# Whisker_Stimulator.net
KiCad netlist of a schematic drawn in EAGLE
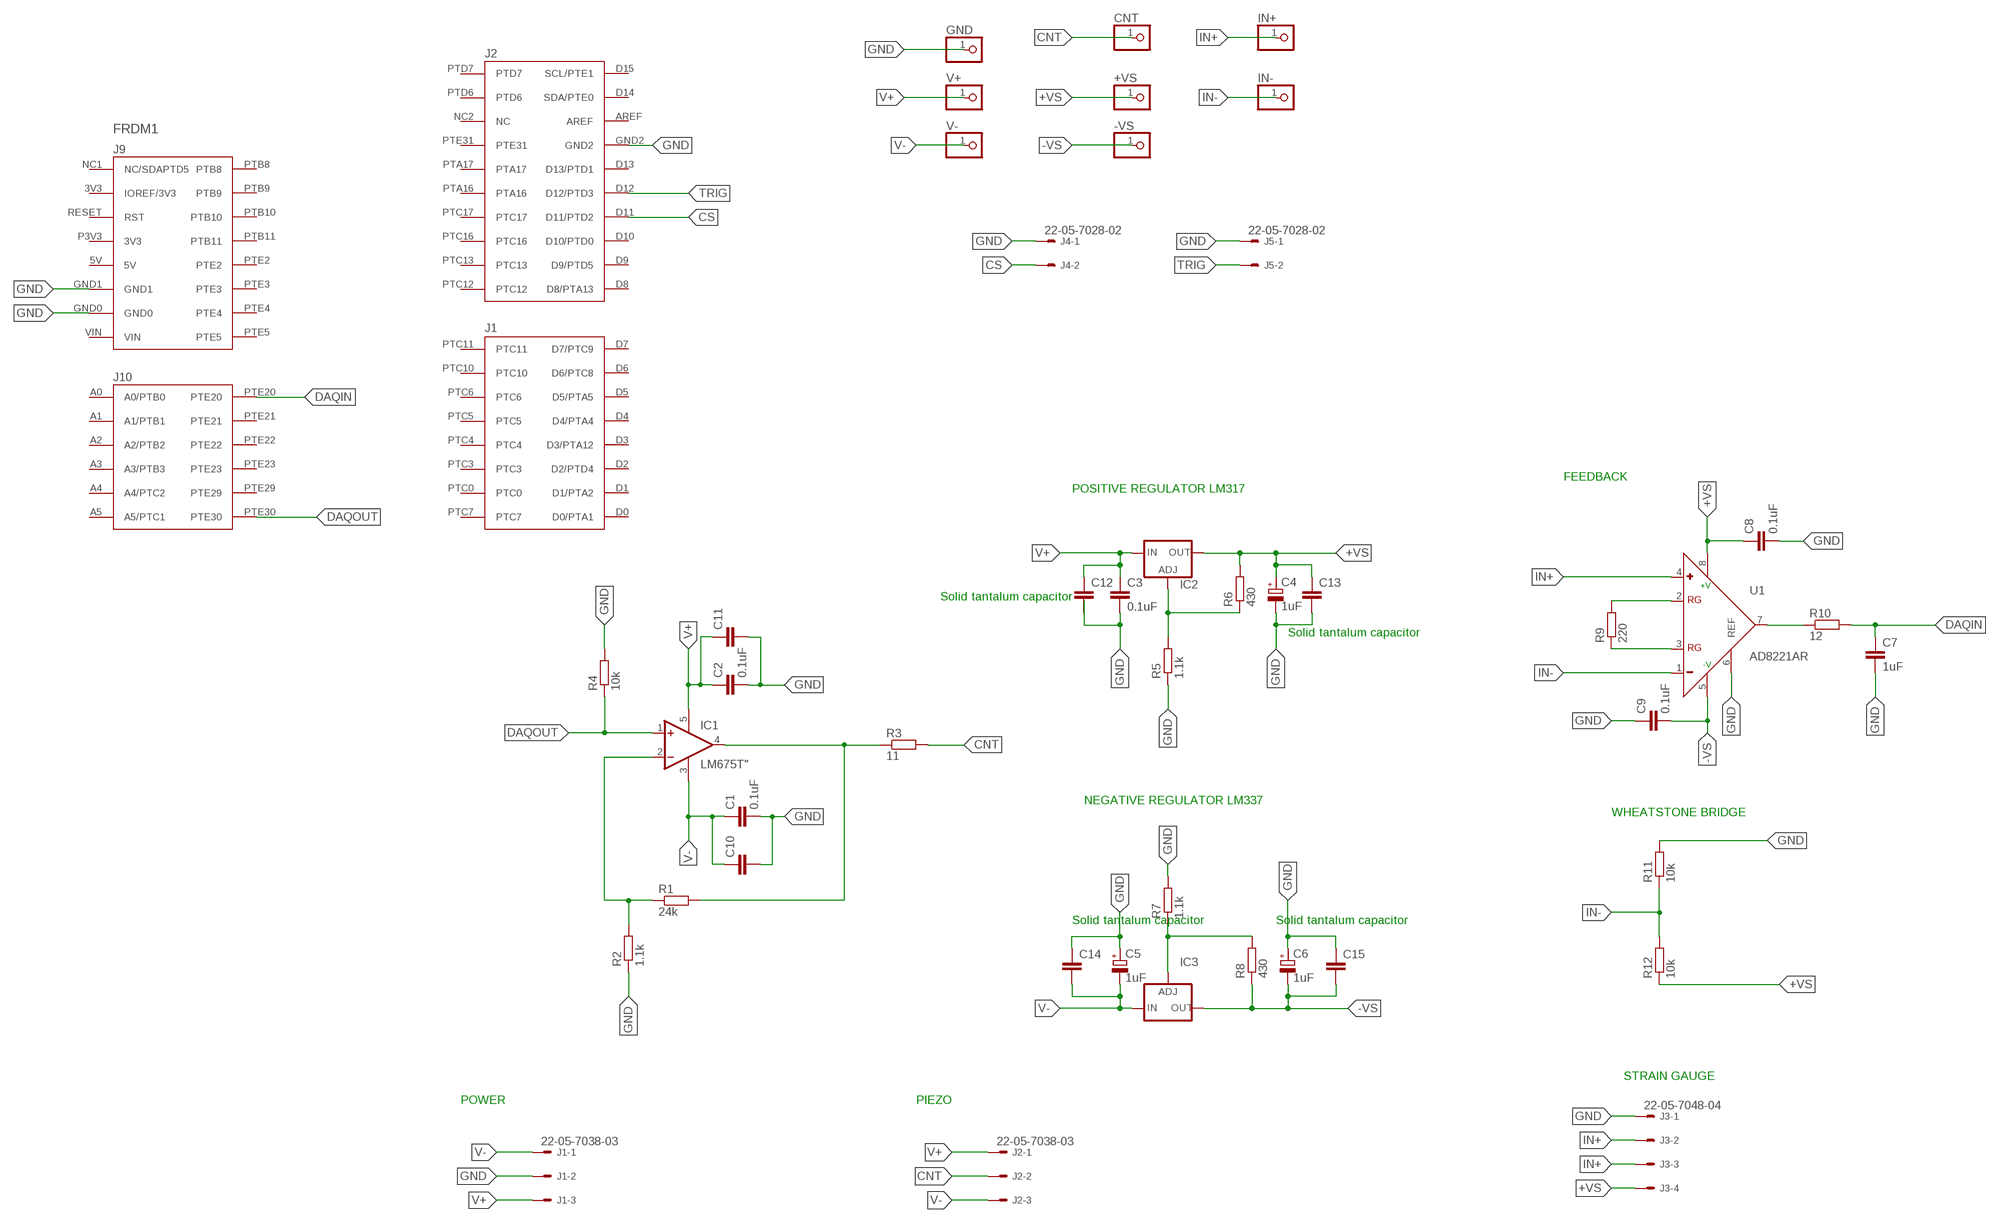
[diagram p0: schematic, sheet 1]

(export (version "E")
  (design (tool "Eeschema 10.0.6"))
  (components
    (comp (ref "+VS")
      (value "PINHD-1X1")
      (footprint "eagle-import:1X01")
      (libsource (lib "eagle-import") (part "PINHD-1X1"))
    )
    (comp (ref "-VS")
      (value "PINHD-1X1")
      (footprint "eagle-import:1X01")
      (libsource (lib "eagle-import") (part "PINHD-1X1"))
    )
    (comp (ref "C1")
      (value "0.1uF")
      (footprint "eagle-import:C0805")
      (libsource (lib "eagle-import") (part "C-EUC0805"))
    )
    (comp (ref "C2")
      (value "0.1uF")
      (footprint "eagle-import:C0805")
      (libsource (lib "eagle-import") (part "C-EUC0805"))
    )
    (comp (ref "C3")
      (value "0.1uF")
      (footprint "eagle-import:C0805")
      (libsource (lib "eagle-import") (part "C-EUC0805"))
    )
    (comp (ref "C4")
      (value "1uF")
      (footprint "eagle-import:E2,5RE")
      (libsource (lib "eagle-import") (part "CPOL-EUE2.5-4V"))
    )
    (comp (ref "C5")
      (value "1uF")
      (footprint "eagle-import:E2,5RE")
      (libsource (lib "eagle-import") (part "CPOL-EUE2.5-4V"))
    )
    (comp (ref "C6")
      (value "1uF")
      (footprint "eagle-import:E2,5RE")
      (libsource (lib "eagle-import") (part "CPOL-EUE2.5-4V"))
    )
    (comp (ref "C7")
      (value "1uF")
      (footprint "eagle-import:C0805")
      (libsource (lib "eagle-import") (part "C-EUC0805"))
    )
    (comp (ref "C8")
      (value "0.1uF")
      (footprint "eagle-import:C0805")
      (libsource (lib "eagle-import") (part "C-EUC0805"))
    )
    (comp (ref "C9")
      (value "0.1uF")
      (footprint "eagle-import:C0805")
      (libsource (lib "eagle-import") (part "C-EUC0805"))
    )
    (comp (ref "C10")
      (value "0.1uF")
      (footprint "eagle-import:C050-024X044")
      (libsource (lib "eagle-import") (part "C-EU050-024X044"))
    )
    (comp (ref "C11")
      (value "0.1uF")
      (footprint "eagle-import:C050-024X044")
      (libsource (lib "eagle-import") (part "C-EU050-024X044"))
    )
    (comp (ref "C12")
      (value "0.1uF")
      (footprint "eagle-import:C050-024X044")
      (libsource (lib "eagle-import") (part "C-EU050-024X044"))
    )
    (comp (ref "C13")
      (value "0.1uF")
      (footprint "eagle-import:C050-024X044")
      (libsource (lib "eagle-import") (part "C-EU050-024X044"))
    )
    (comp (ref "C14")
      (value "0.1uF")
      (footprint "eagle-import:C050-024X044")
      (libsource (lib "eagle-import") (part "C-EU050-024X044"))
    )
    (comp (ref "C15")
      (value "0.1uF")
      (footprint "eagle-import:C050-024X044")
      (libsource (lib "eagle-import") (part "C-EU050-024X044"))
    )
    (comp (ref "CNT")
      (value "PINHD-1X1")
      (footprint "eagle-import:1X01")
      (libsource (lib "eagle-import") (part "PINHD-1X1"))
    )
    (comp (ref "FRDM1")
      (value "FRDM-KL25ZNORMAL")
      (footprint "eagle-import:FRDM_KL25Z_NORMAL")
      (libsource (lib "eagle-import") (part "FRDM-KL25ZNORMAL"))
    )
    (comp (ref "GND")
      (value "PINHD-1X1")
      (footprint "eagle-import:1X01")
      (libsource (lib "eagle-import") (part "PINHD-1X1"))
    )
    (comp (ref "IC1")
      (value "LM675T\"")
      (footprint "eagle-import:CB360")
      (libsource (lib "eagle-import") (part "LM675T{dblquote}"))
    )
    (comp (ref "IC2")
      (value "LM317TS")
      (footprint "eagle-import:317TS")
      (libsource (lib "eagle-import") (part "LM317TS"))
    )
    (comp (ref "IC3")
      (value "LM337TS")
      (footprint "eagle-import:337TS")
      (libsource (lib "eagle-import") (part "LM337TS"))
    )
    (comp (ref "IN+")
      (value "PINHD-1X1")
      (footprint "eagle-import:1X01")
      (libsource (lib "eagle-import") (part "PINHD-1X1"))
    )
    (comp (ref "IN-")
      (value "PINHD-1X1")
      (footprint "eagle-import:1X01")
      (libsource (lib "eagle-import") (part "PINHD-1X1"))
    )
    (comp (ref "J1")
      (value "22-05-7038-03")
      (footprint "eagle-import:7395-03")
      (libsource (lib "eagle-import") (part "22-?-0305-7038"))
    )
    (comp (ref "J2")
      (value "22-05-7038-03")
      (footprint "eagle-import:7395-03")
      (libsource (lib "eagle-import") (part "22-?-0305-7038"))
    )
    (comp (ref "J3")
      (value "22-05-7048-04")
      (footprint "eagle-import:7395-04")
      (libsource (lib "eagle-import") (part "22-?-0405-7048"))
    )
    (comp (ref "J4")
      (value "22-05-7028-02")
      (footprint "eagle-import:7395-02")
      (libsource (lib "eagle-import") (part "22-?-0205-7028"))
    )
    (comp (ref "J5")
      (value "22-05-7028-02")
      (footprint "eagle-import:7395-02")
      (libsource (lib "eagle-import") (part "22-?-0205-7028"))
    )
    (comp (ref "R1")
      (value "24k")
      (footprint "eagle-import:R0805")
      (libsource (lib "eagle-import") (part "R-EU_R0805"))
    )
    (comp (ref "R2")
      (value "1.1k")
      (footprint "eagle-import:R0805")
      (libsource (lib "eagle-import") (part "R-EU_R0805"))
    )
    (comp (ref "R3")
      (value "11")
      (footprint "eagle-import:VMTA55")
      (libsource (lib "eagle-import") (part "R-EU_VMTA55"))
    )
    (comp (ref "R4")
      (value "10k")
      (footprint "eagle-import:R0805")
      (libsource (lib "eagle-import") (part "R-EU_R0805"))
    )
    (comp (ref "R5")
      (value "1.1k")
      (footprint "eagle-import:R0805")
      (libsource (lib "eagle-import") (part "R-EU_R0805"))
    )
    (comp (ref "R6")
      (value "430")
      (footprint "eagle-import:R0805")
      (libsource (lib "eagle-import") (part "R-EU_R0805"))
    )
    (comp (ref "R7")
      (value "1.1k")
      (footprint "eagle-import:R0805")
      (libsource (lib "eagle-import") (part "R-EU_R0805"))
    )
    (comp (ref "R8")
      (value "430")
      (footprint "eagle-import:R0805")
      (libsource (lib "eagle-import") (part "R-EU_R0805"))
    )
    (comp (ref "R9")
      (value "220")
      (footprint "eagle-import:R0805")
      (libsource (lib "eagle-import") (part "R-EU_R0805"))
    )
    (comp (ref "R10")
      (value "12")
      (footprint "eagle-import:R0805")
      (libsource (lib "eagle-import") (part "R-EU_R0805"))
    )
    (comp (ref "R11")
      (value "10k")
      (footprint "eagle-import:R0805")
      (libsource (lib "eagle-import") (part "R-EU_R0805"))
    )
    (comp (ref "R12")
      (value "10k")
      (footprint "eagle-import:R0805")
      (libsource (lib "eagle-import") (part "R-EU_R0805"))
    )
    (comp (ref "U1")
      (value "AD8221AR")
      (footprint "eagle-import:SO8")
      (libsource (lib "eagle-import") (part "AD8221AR"))
    )
    (comp (ref "V+")
      (value "PINHD-1X1")
      (footprint "eagle-import:1X01")
      (libsource (lib "eagle-import") (part "PINHD-1X1"))
    )
    (comp (ref "V-")
      (value "PINHD-1X1")
      (footprint "eagle-import:1X01")
      (libsource (lib "eagle-import") (part "PINHD-1X1"))
    )
  )
  (nets
    (net (code "1") (name "+VS") (class "Default")
      (node (ref "+VS") (pin "1") (pinfunction "1_1") (pintype "passive"))
      (node (ref "C13") (pin "1") (pinfunction "1_1") (pintype "passive"))
      (node (ref "C4") (pin "+") (pinfunction "+_+") (pintype "passive"))
      (node (ref "C8") (pin "1") (pinfunction "1_1") (pintype "passive"))
      (node (ref "IC2") (pin "2") (pinfunction "OUT_2") (pintype "passive"))
      (node (ref "J3") (pin "4") (pinfunction "S_4") (pintype "passive"))
      (node (ref "R12") (pin "1") (pinfunction "1_1") (pintype "passive"))
      (node (ref "R6") (pin "2") (pinfunction "2_2") (pintype "passive"))
      (node (ref "U1") (pin "8") (pinfunction "+V_8") (pintype "power_in"))
    )
    (net (code "2") (name "-VS") (class "Default")
      (node (ref "-VS") (pin "1") (pinfunction "1_1") (pintype "passive"))
      (node (ref "C15") (pin "2") (pinfunction "2_2") (pintype "passive"))
      (node (ref "C6") (pin "-") (pinfunction "-_-") (pintype "passive"))
      (node (ref "C9") (pin "2") (pinfunction "2_2") (pintype "passive"))
      (node (ref "IC3") (pin "3") (pinfunction "OUT_3") (pintype "passive"))
      (node (ref "R8") (pin "1") (pinfunction "1_1") (pintype "passive"))
      (node (ref "U1") (pin "5") (pinfunction "-V_5") (pintype "power_in"))
    )
    (net (code "3") (name "CNT") (class "Default")
      (node (ref "CNT") (pin "1") (pinfunction "1_1") (pintype "passive"))
      (node (ref "J2") (pin "2") (pinfunction "S_2") (pintype "passive"))
      (node (ref "R3") (pin "2") (pinfunction "2_2") (pintype "passive"))
    )
    (net (code "4") (name "CS") (class "Default")
      (node (ref "FRDM1") (pin "D11") (pinfunction "D11/PTD2_D11") (pintype "bidirectional"))
      (node (ref "J4") (pin "2") (pinfunction "S_2") (pintype "passive"))
    )
    (net (code "5") (name "DAQIN") (class "Default")
      (node (ref "C7") (pin "1") (pinfunction "1_1") (pintype "passive"))
      (node (ref "FRDM1") (pin "PTE20") (pinfunction "PTE20_PTE20") (pintype "bidirectional"))
      (node (ref "R10") (pin "2") (pinfunction "2_2") (pintype "passive"))
    )
    (net (code "6") (name "DAQOUT") (class "Default")
      (node (ref "FRDM1") (pin "PTE30") (pinfunction "PTE30_PTE30") (pintype "bidirectional"))
      (node (ref "IC1") (pin "1") (pinfunction "+IN_1") (pintype "input"))
      (node (ref "R4") (pin "1") (pinfunction "1_1") (pintype "passive"))
    )
    (net (code "7") (name "GND") (class "Default")
      (node (ref "C1") (pin "2") (pinfunction "2_2") (pintype "passive"))
      (node (ref "C10") (pin "2") (pinfunction "2_2") (pintype "passive"))
      (node (ref "C11") (pin "2") (pinfunction "2_2") (pintype "passive"))
      (node (ref "C12") (pin "2") (pinfunction "2_2") (pintype "passive"))
      (node (ref "C13") (pin "2") (pinfunction "2_2") (pintype "passive"))
      (node (ref "C14") (pin "1") (pinfunction "1_1") (pintype "passive"))
      (node (ref "C15") (pin "1") (pinfunction "1_1") (pintype "passive"))
      (node (ref "C2") (pin "2") (pinfunction "2_2") (pintype "passive"))
      (node (ref "C3") (pin "2") (pinfunction "2_2") (pintype "passive"))
      (node (ref "C4") (pin "-") (pinfunction "-_-") (pintype "passive"))
      (node (ref "C5") (pin "+") (pinfunction "+_+") (pintype "passive"))
      (node (ref "C6") (pin "+") (pinfunction "+_+") (pintype "passive"))
      (node (ref "C7") (pin "2") (pinfunction "2_2") (pintype "passive"))
      (node (ref "C8") (pin "2") (pinfunction "2_2") (pintype "passive"))
      (node (ref "C9") (pin "1") (pinfunction "1_1") (pintype "passive"))
      (node (ref "FRDM1") (pin "GND0") (pinfunction "GND0_GND0") (pintype "bidirectional"))
      (node (ref "FRDM1") (pin "GND1") (pinfunction "GND1_GND1") (pintype "bidirectional"))
      (node (ref "FRDM1") (pin "GND2") (pinfunction "GND2_GND2") (pintype "bidirectional"))
      (node (ref "GND") (pin "1") (pinfunction "1_1") (pintype "passive"))
      (node (ref "J1") (pin "2") (pinfunction "S_2") (pintype "passive"))
      (node (ref "J3") (pin "1") (pinfunction "S_1") (pintype "passive"))
      (node (ref "J4") (pin "1") (pinfunction "S_1") (pintype "passive"))
      (node (ref "J5") (pin "1") (pinfunction "S_1") (pintype "passive"))
      (node (ref "R11") (pin "2") (pinfunction "2_2") (pintype "passive"))
      (node (ref "R2") (pin "1") (pinfunction "1_1") (pintype "passive"))
      (node (ref "R4") (pin "2") (pinfunction "2_2") (pintype "passive"))
      (node (ref "R5") (pin "1") (pinfunction "1_1") (pintype "passive"))
      (node (ref "R7") (pin "2") (pinfunction "2_2") (pintype "passive"))
      (node (ref "U1") (pin "6") (pinfunction "REF_6") (pintype "passive"))
    )
    (net (code "8") (name "IN+") (class "Default")
      (node (ref "IN+") (pin "1") (pinfunction "1_1") (pintype "passive"))
      (node (ref "J3") (pin "2") (pinfunction "S_2") (pintype "passive"))
      (node (ref "J3") (pin "3") (pinfunction "S_3") (pintype "passive"))
      (node (ref "U1") (pin "4") (pinfunction "+_4") (pintype "input"))
    )
    (net (code "9") (name "IN-") (class "Default")
      (node (ref "IN-") (pin "1") (pinfunction "1_1") (pintype "passive"))
      (node (ref "R11") (pin "1") (pinfunction "1_1") (pintype "passive"))
      (node (ref "R12") (pin "2") (pinfunction "2_2") (pintype "passive"))
      (node (ref "U1") (pin "1") (pinfunction "-_1") (pintype "input"))
    )
    (net (code "10") (name "Net-(IC1--IN)") (class "Default")
      (node (ref "IC1") (pin "2") (pinfunction "-IN_2") (pintype "input"))
      (node (ref "R1") (pin "1") (pinfunction "1_1") (pintype "passive"))
      (node (ref "R2") (pin "2") (pinfunction "2_2") (pintype "passive"))
    )
    (net (code "11") (name "Net-(IC1-OUT)") (class "Default")
      (node (ref "IC1") (pin "4") (pinfunction "OUT_4") (pintype "output"))
      (node (ref "R1") (pin "2") (pinfunction "2_2") (pintype "passive"))
      (node (ref "R3") (pin "1") (pinfunction "1_1") (pintype "passive"))
    )
    (net (code "12") (name "Net-(IC2-ADJ)") (class "Default")
      (node (ref "IC2") (pin "1") (pinfunction "ADJ_1") (pintype "input"))
      (node (ref "R5") (pin "2") (pinfunction "2_2") (pintype "passive"))
      (node (ref "R6") (pin "1") (pinfunction "1_1") (pintype "passive"))
    )
    (net (code "13") (name "Net-(IC3-ADJ)") (class "Default")
      (node (ref "IC3") (pin "1") (pinfunction "ADJ_1") (pintype "input"))
      (node (ref "R7") (pin "1") (pinfunction "1_1") (pintype "passive"))
      (node (ref "R8") (pin "2") (pinfunction "2_2") (pintype "passive"))
    )
    (net (code "14") (name "Net-(R9-Pad1)") (class "Default")
      (node (ref "R9") (pin "1") (pinfunction "1_1") (pintype "passive"))
      (node (ref "U1") (pin "3") (pinfunction "RG_3") (pintype "passive"))
    )
    (net (code "15") (name "Net-(R9-Pad2)") (class "Default")
      (node (ref "R9") (pin "2") (pinfunction "2_2") (pintype "passive"))
      (node (ref "U1") (pin "2") (pinfunction "RG_2") (pintype "passive"))
    )
    (net (code "16") (name "Net-(U1-OUT)") (class "Default")
      (node (ref "R10") (pin "1") (pinfunction "1_1") (pintype "passive"))
      (node (ref "U1") (pin "7") (pinfunction "OUT_7") (pintype "output"))
    )
    (net (code "17") (name "TRIG") (class "Default")
      (node (ref "FRDM1") (pin "D12") (pinfunction "D12/PTD3_D12") (pintype "bidirectional"))
      (node (ref "J5") (pin "2") (pinfunction "S_2") (pintype "passive"))
    )
    (net (code "18") (name "V+") (class "Default")
      (node (ref "C11") (pin "1") (pinfunction "1_1") (pintype "passive"))
      (node (ref "C12") (pin "1") (pinfunction "1_1") (pintype "passive"))
      (node (ref "C2") (pin "1") (pinfunction "1_1") (pintype "passive"))
      (node (ref "C3") (pin "1") (pinfunction "1_1") (pintype "passive"))
      (node (ref "IC1") (pin "5") (pinfunction "V+_5") (pintype "power_in"))
      (node (ref "IC2") (pin "3") (pinfunction "IN_3") (pintype "input"))
      (node (ref "J1") (pin "3") (pinfunction "S_3") (pintype "passive"))
      (node (ref "J2") (pin "1") (pinfunction "S_1") (pintype "passive"))
      (node (ref "V+") (pin "1") (pinfunction "1_1") (pintype "passive"))
    )
    (net (code "19") (name "V-") (class "Default")
      (node (ref "C1") (pin "1") (pinfunction "1_1") (pintype "passive"))
      (node (ref "C10") (pin "1") (pinfunction "1_1") (pintype "passive"))
      (node (ref "C14") (pin "2") (pinfunction "2_2") (pintype "passive"))
      (node (ref "C5") (pin "-") (pinfunction "-_-") (pintype "passive"))
      (node (ref "IC1") (pin "3") (pinfunction "V-_3") (pintype "power_in"))
      (node (ref "IC3") (pin "2") (pinfunction "IN_2") (pintype "input"))
      (node (ref "J1") (pin "1") (pinfunction "S_1") (pintype "passive"))
      (node (ref "J2") (pin "3") (pinfunction "S_3") (pintype "passive"))
      (node (ref "V-") (pin "1") (pinfunction "1_1") (pintype "passive"))
    )
    (net (code "20") (name "unconnected-(FRDM1-3V3-PadP3V3)") (class "Default")
      (node (ref "FRDM1") (pin "P3V3") (pinfunction "3V3_P3V3") (pintype "bidirectional"))
    )
    (net (code "21") (name "unconnected-(FRDM1-A0{slash}PTB0-PadA0)") (class "Default")
      (node (ref "FRDM1") (pin "A0") (pinfunction "A0/PTB0_A0") (pintype "bidirectional"))
    )
    (net (code "22") (name "unconnected-(FRDM1-A1{slash}PTB1-PadA1)") (class "Default")
      (node (ref "FRDM1") (pin "A1") (pinfunction "A1/PTB1_A1") (pintype "bidirectional"))
    )
    (net (code "23") (name "unconnected-(FRDM1-A2{slash}PTB2-PadA2)") (class "Default")
      (node (ref "FRDM1") (pin "A2") (pinfunction "A2/PTB2_A2") (pintype "bidirectional"))
    )
    (net (code "24") (name "unconnected-(FRDM1-A3{slash}PTB3-PadA3)") (class "Default")
      (node (ref "FRDM1") (pin "A3") (pinfunction "A3/PTB3_A3") (pintype "bidirectional"))
    )
    (net (code "25") (name "unconnected-(FRDM1-A4{slash}PTC2-PadA4)") (class "Default")
      (node (ref "FRDM1") (pin "A4") (pinfunction "A4/PTC2_A4") (pintype "bidirectional"))
    )
    (net (code "26") (name "unconnected-(FRDM1-A5{slash}PTC1-PadA5)") (class "Default")
      (node (ref "FRDM1") (pin "A5") (pinfunction "A5/PTC1_A5") (pintype "bidirectional"))
    )
    (net (code "27") (name "unconnected-(FRDM1-D0{slash}PTA1-PadD0)") (class "Default")
      (node (ref "FRDM1") (pin "D0") (pinfunction "D0/PTA1_D0") (pintype "bidirectional"))
    )
    (net (code "28") (name "unconnected-(FRDM1-D1{slash}PTA2-PadD1)") (class "Default")
      (node (ref "FRDM1") (pin "D1") (pinfunction "D1/PTA2_D1") (pintype "bidirectional"))
    )
    (net (code "29") (name "unconnected-(FRDM1-D2{slash}PTD4-PadD2)") (class "Default")
      (node (ref "FRDM1") (pin "D2") (pinfunction "D2/PTD4_D2") (pintype "bidirectional"))
    )
    (net (code "30") (name "unconnected-(FRDM1-D3{slash}PTA12-PadD3)") (class "Default")
      (node (ref "FRDM1") (pin "D3") (pinfunction "D3/PTA12_D3") (pintype "bidirectional"))
    )
    (net (code "31") (name "unconnected-(FRDM1-D4{slash}PTA4-PadD4)") (class "Default")
      (node (ref "FRDM1") (pin "D4") (pinfunction "D4/PTA4_D4") (pintype "bidirectional"))
    )
    (net (code "32") (name "unconnected-(FRDM1-D5{slash}PTA5-PadD5)") (class "Default")
      (node (ref "FRDM1") (pin "D5") (pinfunction "D5/PTA5_D5") (pintype "bidirectional"))
    )
    (net (code "33") (name "unconnected-(FRDM1-D6{slash}PTC8-PadD6)") (class "Default")
      (node (ref "FRDM1") (pin "D6") (pinfunction "D6/PTC8_D6") (pintype "bidirectional"))
    )
    (net (code "34") (name "unconnected-(FRDM1-D7{slash}PTC9-PadD7)") (class "Default")
      (node (ref "FRDM1") (pin "D7") (pinfunction "D7/PTC9_D7") (pintype "bidirectional"))
    )
    (net (code "35") (name "unconnected-(FRDM1-D8{slash}PTA13-PadD8)") (class "Default")
      (node (ref "FRDM1") (pin "D8") (pinfunction "D8/PTA13_D8") (pintype "bidirectional"))
    )
    (net (code "36") (name "unconnected-(FRDM1-D9{slash}PTD5-PadD9)") (class "Default")
      (node (ref "FRDM1") (pin "D9") (pinfunction "D9/PTD5_D9") (pintype "bidirectional"))
    )
    (net (code "37") (name "unconnected-(FRDM1-D10{slash}PTD0-PadD10)") (class "Default")
      (node (ref "FRDM1") (pin "D10") (pinfunction "D10/PTD0_D10") (pintype "bidirectional"))
    )
    (net (code "38") (name "unconnected-(FRDM1-D13{slash}PTD1-PadD13)") (class "Default")
      (node (ref "FRDM1") (pin "D13") (pinfunction "D13/PTD1_D13") (pintype "bidirectional"))
    )
    (net (code "39") (name "unconnected-(FRDM1-IOREF{slash}3V3-Pad3V3)") (class "Default")
      (node (ref "FRDM1") (pin "3V3") (pinfunction "IOREF/3V3_3V3") (pintype "bidirectional"))
    )
    (net (code "40") (name "unconnected-(FRDM1-NC-PadNC2)") (class "Default")
      (node (ref "FRDM1") (pin "NC2") (pinfunction "NC_NC2") (pintype "bidirectional"))
    )
    (net (code "41") (name "unconnected-(FRDM1-NC{slash}SDAPTD5-PadNC1)") (class "Default")
      (node (ref "FRDM1") (pin "NC1") (pinfunction "NC/SDAPTD5_NC1") (pintype "bidirectional"))
    )
    (net (code "42") (name "unconnected-(FRDM1-Pad5V)") (class "Default")
      (node (ref "FRDM1") (pin "5V") (pinfunction "5V_5V") (pintype "bidirectional"))
    )
    (net (code "43") (name "unconnected-(FRDM1-PadAREF)") (class "Default")
      (node (ref "FRDM1") (pin "AREF") (pinfunction "AREF_AREF") (pintype "bidirectional"))
    )
    (net (code "44") (name "unconnected-(FRDM1-PadPTA16)") (class "Default")
      (node (ref "FRDM1") (pin "PTA16") (pinfunction "PTA16_PTA16") (pintype "bidirectional"))
    )
    (net (code "45") (name "unconnected-(FRDM1-PadPTA17)") (class "Default")
      (node (ref "FRDM1") (pin "PTA17") (pinfunction "PTA17_PTA17") (pintype "bidirectional"))
    )
    (net (code "46") (name "unconnected-(FRDM1-PadPTB8)") (class "Default")
      (node (ref "FRDM1") (pin "PTB8") (pinfunction "PTB8_PTB8") (pintype "bidirectional"))
    )
    (net (code "47") (name "unconnected-(FRDM1-PadPTB9)") (class "Default")
      (node (ref "FRDM1") (pin "PTB9") (pinfunction "PTB9_PTB9") (pintype "bidirectional"))
    )
    (net (code "48") (name "unconnected-(FRDM1-PadPTB10)") (class "Default")
      (node (ref "FRDM1") (pin "PTB10") (pinfunction "PTB10_PTB10") (pintype "bidirectional"))
    )
    (net (code "49") (name "unconnected-(FRDM1-PadPTB11)") (class "Default")
      (node (ref "FRDM1") (pin "PTB11") (pinfunction "PTB11_PTB11") (pintype "bidirectional"))
    )
    (net (code "50") (name "unconnected-(FRDM1-PadPTC0)") (class "Default")
      (node (ref "FRDM1") (pin "PTC0") (pinfunction "PTC0_PTC0") (pintype "bidirectional"))
    )
    (net (code "51") (name "unconnected-(FRDM1-PadPTC3)") (class "Default")
      (node (ref "FRDM1") (pin "PTC3") (pinfunction "PTC3_PTC3") (pintype "bidirectional"))
    )
    (net (code "52") (name "unconnected-(FRDM1-PadPTC4)") (class "Default")
      (node (ref "FRDM1") (pin "PTC4") (pinfunction "PTC4_PTC4") (pintype "bidirectional"))
    )
    (net (code "53") (name "unconnected-(FRDM1-PadPTC5)") (class "Default")
      (node (ref "FRDM1") (pin "PTC5") (pinfunction "PTC5_PTC5") (pintype "bidirectional"))
    )
    (net (code "54") (name "unconnected-(FRDM1-PadPTC6)") (class "Default")
      (node (ref "FRDM1") (pin "PTC6") (pinfunction "PTC6_PTC6") (pintype "bidirectional"))
    )
    (net (code "55") (name "unconnected-(FRDM1-PadPTC7)") (class "Default")
      (node (ref "FRDM1") (pin "PTC7") (pinfunction "PTC7_PTC7") (pintype "bidirectional"))
    )
    (net (code "56") (name "unconnected-(FRDM1-PadPTC10)") (class "Default")
      (node (ref "FRDM1") (pin "PTC10") (pinfunction "PTC10_PTC10") (pintype "bidirectional"))
    )
    (net (code "57") (name "unconnected-(FRDM1-PadPTC11)") (class "Default")
      (node (ref "FRDM1") (pin "PTC11") (pinfunction "PTC11_PTC11") (pintype "bidirectional"))
    )
    (net (code "58") (name "unconnected-(FRDM1-PadPTC12)") (class "Default")
      (node (ref "FRDM1") (pin "PTC12") (pinfunction "PTC12_PTC12") (pintype "bidirectional"))
    )
    (net (code "59") (name "unconnected-(FRDM1-PadPTC13)") (class "Default")
      (node (ref "FRDM1") (pin "PTC13") (pinfunction "PTC13_PTC13") (pintype "bidirectional"))
    )
    (net (code "60") (name "unconnected-(FRDM1-PadPTC16)") (class "Default")
      (node (ref "FRDM1") (pin "PTC16") (pinfunction "PTC16_PTC16") (pintype "bidirectional"))
    )
    (net (code "61") (name "unconnected-(FRDM1-PadPTC17)") (class "Default")
      (node (ref "FRDM1") (pin "PTC17") (pinfunction "PTC17_PTC17") (pintype "bidirectional"))
    )
    (net (code "62") (name "unconnected-(FRDM1-PadPTD6)") (class "Default")
      (node (ref "FRDM1") (pin "PTD6") (pinfunction "PTD6_PTD6") (pintype "bidirectional"))
    )
    (net (code "63") (name "unconnected-(FRDM1-PadPTD7)") (class "Default")
      (node (ref "FRDM1") (pin "PTD7") (pinfunction "PTD7_PTD7") (pintype "bidirectional"))
    )
    (net (code "64") (name "unconnected-(FRDM1-PadPTE2)") (class "Default")
      (node (ref "FRDM1") (pin "PTE2") (pinfunction "PTE2_PTE2") (pintype "bidirectional"))
    )
    (net (code "65") (name "unconnected-(FRDM1-PadPTE3)") (class "Default")
      (node (ref "FRDM1") (pin "PTE3") (pinfunction "PTE3_PTE3") (pintype "bidirectional"))
    )
    (net (code "66") (name "unconnected-(FRDM1-PadPTE4)") (class "Default")
      (node (ref "FRDM1") (pin "PTE4") (pinfunction "PTE4_PTE4") (pintype "bidirectional"))
    )
    (net (code "67") (name "unconnected-(FRDM1-PadPTE5)") (class "Default")
      (node (ref "FRDM1") (pin "PTE5") (pinfunction "PTE5_PTE5") (pintype "bidirectional"))
    )
    (net (code "68") (name "unconnected-(FRDM1-PadPTE21)") (class "Default")
      (node (ref "FRDM1") (pin "PTE21") (pinfunction "PTE21_PTE21") (pintype "bidirectional"))
    )
    (net (code "69") (name "unconnected-(FRDM1-PadPTE22)") (class "Default")
      (node (ref "FRDM1") (pin "PTE22") (pinfunction "PTE22_PTE22") (pintype "bidirectional"))
    )
    (net (code "70") (name "unconnected-(FRDM1-PadPTE23)") (class "Default")
      (node (ref "FRDM1") (pin "PTE23") (pinfunction "PTE23_PTE23") (pintype "bidirectional"))
    )
    (net (code "71") (name "unconnected-(FRDM1-PadPTE29)") (class "Default")
      (node (ref "FRDM1") (pin "PTE29") (pinfunction "PTE29_PTE29") (pintype "bidirectional"))
    )
    (net (code "72") (name "unconnected-(FRDM1-PadPTE31)") (class "Default")
      (node (ref "FRDM1") (pin "PTE31") (pinfunction "PTE31_PTE31") (pintype "bidirectional"))
    )
    (net (code "73") (name "unconnected-(FRDM1-PadVIN)") (class "Default")
      (node (ref "FRDM1") (pin "VIN") (pinfunction "VIN_VIN") (pintype "bidirectional"))
    )
    (net (code "74") (name "unconnected-(FRDM1-RST-PadRESET)") (class "Default")
      (node (ref "FRDM1") (pin "RESET") (pinfunction "RST_RESET") (pintype "bidirectional"))
    )
    (net (code "75") (name "unconnected-(FRDM1-SCL{slash}PTE1-PadD15)") (class "Default")
      (node (ref "FRDM1") (pin "D15") (pinfunction "SCL/PTE1_D15") (pintype "bidirectional"))
    )
    (net (code "76") (name "unconnected-(FRDM1-SDA{slash}PTE0-PadD14)") (class "Default")
      (node (ref "FRDM1") (pin "D14") (pinfunction "SDA/PTE0_D14") (pintype "bidirectional"))
    )
  )
)
